# pemasok_air.net
KiCad netlist of a schematic drawn in EAGLE
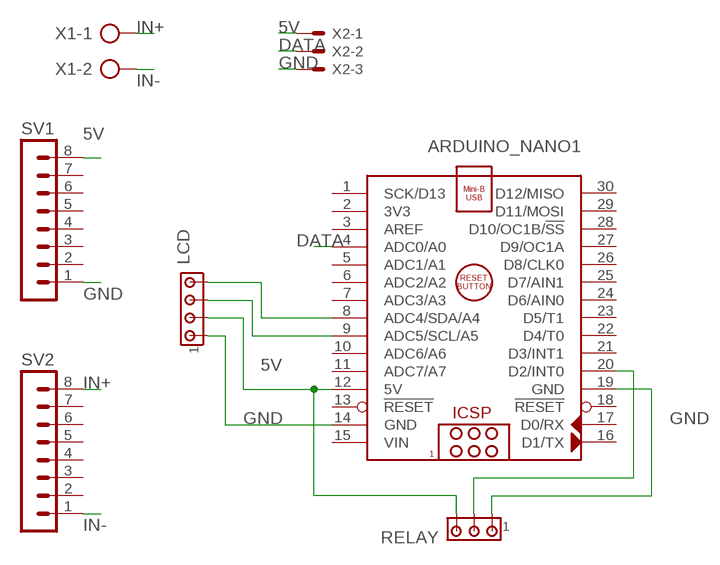
[diagram p0: schematic, sheet 1]

(export (version "E")
  (design (tool "Eeschema 10.0.6"))
  (components
    (comp (ref "ARDUINO_NANO1")
      (value "ARDUINO_NANO")
      (footprint "eagle-import:ARDUINO_NANO")
      (libsource (lib "eagle-import") (part "ARDUINO_NANO"))
    )
    (comp (ref "LCD")
      (value "MTA04-100")
      (footprint "eagle-import:10X04MTA")
      (libsource (lib "eagle-import") (part "MTA04-100"))
    )
    (comp (ref "RELAY")
      (value "MTA03-100")
      (footprint "eagle-import:10X03MTA")
      (libsource (lib "eagle-import") (part "MTA03-100"))
    )
    (comp (ref "SV1")
      (value "MA08-1")
      (footprint "eagle-import:MA08-1")
      (libsource (lib "eagle-import") (part "MA08-1"))
    )
    (comp (ref "SV2")
      (value "MA08-1")
      (footprint "eagle-import:MA08-1")
      (libsource (lib "eagle-import") (part "MA08-1"))
    )
    (comp (ref "X1")
      (value "AK500/2-H")
      (footprint "eagle-import:AK500_2-H")
      (libsource (lib "eagle-import") (part "AK500/2-H"))
    )
    (comp (ref "X2")
      (value "KK-156-3")
      (footprint "eagle-import:KK-156-3")
      (fields (field (name "MF") "MOLEX"))
      (libsource (lib "eagle-import") (part "KK-156-3"))
    )
  )
  (nets
    (net (code "1") (name "/5V") (class "Default")
      (node (ref "ARDUINO_NANO1") (pin "12") (pinfunction "5V_12") (pintype "power_in"))
      (node (ref "LCD") (pin "2") (pinfunction "2_2") (pintype "passive"))
      (node (ref "RELAY") (pin "3") (pinfunction "3_3") (pintype "passive"))
      (node (ref "SV1") (pin "8") (pinfunction "8_8") (pintype "passive"))
      (node (ref "X2") (pin "1") (pinfunction "S_1") (pintype "passive"))
    )
    (net (code "2") (name "/DATA") (class "Default")
      (node (ref "ARDUINO_NANO1") (pin "4") (pinfunction "ADC0/A0_4") (pintype "bidirectional"))
      (node (ref "X2") (pin "2") (pinfunction "S_2") (pintype "passive"))
    )
    (net (code "3") (name "/GND") (class "Default")
      (node (ref "ARDUINO_NANO1") (pin "14") (pinfunction "GND_14") (pintype "power_in"))
      (node (ref "ARDUINO_NANO1") (pin "19") (pinfunction "GND_19") (pintype "power_in"))
      (node (ref "LCD") (pin "1") (pinfunction "1_1") (pintype "passive"))
      (node (ref "RELAY") (pin "1") (pinfunction "1_1") (pintype "passive"))
      (node (ref "SV1") (pin "1") (pinfunction "1_1") (pintype "passive"))
      (node (ref "X2") (pin "3") (pinfunction "S_3") (pintype "passive"))
    )
    (net (code "4") (name "/IN+") (class "Default")
      (node (ref "SV2") (pin "8") (pinfunction "8_8") (pintype "passive"))
      (node (ref "X1") (pin "1") (pinfunction "KL_1") (pintype "passive"))
    )
    (net (code "5") (name "/IN-") (class "Default")
      (node (ref "SV2") (pin "1") (pinfunction "1_1") (pintype "passive"))
      (node (ref "X1") (pin "2") (pinfunction "KL_2") (pintype "passive"))
    )
    (net (code "6") (name "/VIN") (class "Default")
      (node (ref "ARDUINO_NANO1") (pin "15") (pinfunction "VIN_15") (pintype "power_in"))
    )
    (net (code "7") (name "Net-(ARDUINO_NANO1-ADC4{slash}SDA{slash}A4)") (class "Default")
      (node (ref "ARDUINO_NANO1") (pin "8") (pinfunction "ADC4/SDA/A4_8") (pintype "bidirectional"))
      (node (ref "LCD") (pin "4") (pinfunction "4_4") (pintype "passive"))
    )
    (net (code "8") (name "Net-(ARDUINO_NANO1-ADC5{slash}SCL{slash}A5)") (class "Default")
      (node (ref "ARDUINO_NANO1") (pin "9") (pinfunction "ADC5/SCL/A5_9") (pintype "bidirectional"))
      (node (ref "LCD") (pin "3") (pinfunction "3_3") (pintype "passive"))
    )
    (net (code "9") (name "Net-(ARDUINO_NANO1-D2{slash}INT0)") (class "Default")
      (node (ref "ARDUINO_NANO1") (pin "20") (pinfunction "D2/INT0_20") (pintype "bidirectional"))
      (node (ref "RELAY") (pin "2") (pinfunction "2_2") (pintype "passive"))
    )
    (net (code "10") (name "unconnected-(ARDUINO_NANO1-3V3-Pad2)") (class "Default")
      (node (ref "ARDUINO_NANO1") (pin "2") (pinfunction "3V3_2") (pintype "output"))
    )
    (net (code "11") (name "unconnected-(ARDUINO_NANO1-ADC1{slash}A1-Pad5)") (class "Default")
      (node (ref "ARDUINO_NANO1") (pin "5") (pinfunction "ADC1/A1_5") (pintype "bidirectional"))
    )
    (net (code "12") (name "unconnected-(ARDUINO_NANO1-ADC2{slash}A2-Pad6)") (class "Default")
      (node (ref "ARDUINO_NANO1") (pin "6") (pinfunction "ADC2/A2_6") (pintype "bidirectional"))
    )
    (net (code "13") (name "unconnected-(ARDUINO_NANO1-ADC3{slash}A3-Pad7)") (class "Default")
      (node (ref "ARDUINO_NANO1") (pin "7") (pinfunction "ADC3/A3_7") (pintype "bidirectional"))
    )
    (net (code "14") (name "unconnected-(ARDUINO_NANO1-ADC6{slash}A6-Pad10)") (class "Default")
      (node (ref "ARDUINO_NANO1") (pin "10") (pinfunction "ADC6/A6_10") (pintype "bidirectional"))
    )
    (net (code "15") (name "unconnected-(ARDUINO_NANO1-ADC7{slash}A7-Pad11)") (class "Default")
      (node (ref "ARDUINO_NANO1") (pin "11") (pinfunction "ADC7/A7_11") (pintype "bidirectional"))
    )
    (net (code "16") (name "unconnected-(ARDUINO_NANO1-AREF-Pad3)") (class "Default")
      (node (ref "ARDUINO_NANO1") (pin "3") (pinfunction "AREF_3") (pintype "input"))
    )
    (net (code "17") (name "unconnected-(ARDUINO_NANO1-D0{slash}RX-Pad17)") (class "Default")
      (node (ref "ARDUINO_NANO1") (pin "17") (pinfunction "D0/RX_17") (pintype "bidirectional"))
    )
    (net (code "18") (name "unconnected-(ARDUINO_NANO1-D1{slash}TX-Pad16)") (class "Default")
      (node (ref "ARDUINO_NANO1") (pin "16") (pinfunction "D1/TX_16") (pintype "bidirectional"))
    )
    (net (code "19") (name "unconnected-(ARDUINO_NANO1-D3{slash}INT1-Pad21)") (class "Default")
      (node (ref "ARDUINO_NANO1") (pin "21") (pinfunction "D3/INT1_21") (pintype "bidirectional"))
    )
    (net (code "20") (name "unconnected-(ARDUINO_NANO1-D4{slash}T0-Pad22)") (class "Default")
      (node (ref "ARDUINO_NANO1") (pin "22") (pinfunction "D4/T0_22") (pintype "bidirectional"))
    )
    (net (code "21") (name "unconnected-(ARDUINO_NANO1-D5{slash}T1-Pad23)") (class "Default")
      (node (ref "ARDUINO_NANO1") (pin "23") (pinfunction "D5/T1_23") (pintype "bidirectional"))
    )
    (net (code "22") (name "unconnected-(ARDUINO_NANO1-D6{slash}AIN0-Pad24)") (class "Default")
      (node (ref "ARDUINO_NANO1") (pin "24") (pinfunction "D6/AIN0_24") (pintype "bidirectional"))
    )
    (net (code "23") (name "unconnected-(ARDUINO_NANO1-D7{slash}AIN1-Pad25)") (class "Default")
      (node (ref "ARDUINO_NANO1") (pin "25") (pinfunction "D7/AIN1_25") (pintype "bidirectional"))
    )
    (net (code "24") (name "unconnected-(ARDUINO_NANO1-D8{slash}CLK0-Pad26)") (class "Default")
      (node (ref "ARDUINO_NANO1") (pin "26") (pinfunction "D8/CLK0_26") (pintype "bidirectional"))
    )
    (net (code "25") (name "unconnected-(ARDUINO_NANO1-D9{slash}OC1A-Pad27)") (class "Default")
      (node (ref "ARDUINO_NANO1") (pin "27") (pinfunction "D9/OC1A_27") (pintype "bidirectional"))
    )
    (net (code "26") (name "unconnected-(ARDUINO_NANO1-D10{slash}OC1B{slash}~{SS}-Pad28)") (class "Default")
      (node (ref "ARDUINO_NANO1") (pin "28") (pinfunction "D10/OC1B/~{SS}_28") (pintype "bidirectional"))
    )
    (net (code "27") (name "unconnected-(ARDUINO_NANO1-D11{slash}MOSI-Pad29)") (class "Default")
      (node (ref "ARDUINO_NANO1") (pin "29") (pinfunction "D11/MOSI_29") (pintype "bidirectional"))
    )
    (net (code "28") (name "unconnected-(ARDUINO_NANO1-D12{slash}MISO-Pad30)") (class "Default")
      (node (ref "ARDUINO_NANO1") (pin "30") (pinfunction "D12/MISO_30") (pintype "bidirectional"))
    )
    (net (code "29") (name "unconnected-(ARDUINO_NANO1-SCK{slash}D13-Pad1)") (class "Default")
      (node (ref "ARDUINO_NANO1") (pin "1") (pinfunction "SCK/D13_1") (pintype "bidirectional"))
    )
    (net (code "30") (name "unconnected-(ARDUINO_NANO1-~{RESET}-Pad13)") (class "Default")
      (node (ref "ARDUINO_NANO1") (pin "13") (pinfunction "~{RESET}_13") (pintype "input"))
    )
    (net (code "31") (name "unconnected-(ARDUINO_NANO1-~{RESET}-Pad18)") (class "Default")
      (node (ref "ARDUINO_NANO1") (pin "18") (pinfunction "~{RESET}_18") (pintype "input"))
    )
    (net (code "32") (name "unconnected-(SV1-Pad2)") (class "Default")
      (node (ref "SV1") (pin "2") (pinfunction "2_2") (pintype "passive"))
    )
    (net (code "33") (name "unconnected-(SV1-Pad3)") (class "Default")
      (node (ref "SV1") (pin "3") (pinfunction "3_3") (pintype "passive"))
    )
    (net (code "34") (name "unconnected-(SV1-Pad4)") (class "Default")
      (node (ref "SV1") (pin "4") (pinfunction "4_4") (pintype "passive"))
    )
    (net (code "35") (name "unconnected-(SV1-Pad5)") (class "Default")
      (node (ref "SV1") (pin "5") (pinfunction "5_5") (pintype "passive"))
    )
    (net (code "36") (name "unconnected-(SV1-Pad6)") (class "Default")
      (node (ref "SV1") (pin "6") (pinfunction "6_6") (pintype "passive"))
    )
    (net (code "37") (name "unconnected-(SV1-Pad7)") (class "Default")
      (node (ref "SV1") (pin "7") (pinfunction "7_7") (pintype "passive"))
    )
    (net (code "38") (name "unconnected-(SV2-Pad2)") (class "Default")
      (node (ref "SV2") (pin "2") (pinfunction "2_2") (pintype "passive"))
    )
    (net (code "39") (name "unconnected-(SV2-Pad3)") (class "Default")
      (node (ref "SV2") (pin "3") (pinfunction "3_3") (pintype "passive"))
    )
    (net (code "40") (name "unconnected-(SV2-Pad4)") (class "Default")
      (node (ref "SV2") (pin "4") (pinfunction "4_4") (pintype "passive"))
    )
    (net (code "41") (name "unconnected-(SV2-Pad5)") (class "Default")
      (node (ref "SV2") (pin "5") (pinfunction "5_5") (pintype "passive"))
    )
    (net (code "42") (name "unconnected-(SV2-Pad6)") (class "Default")
      (node (ref "SV2") (pin "6") (pinfunction "6_6") (pintype "passive"))
    )
    (net (code "43") (name "unconnected-(SV2-Pad7)") (class "Default")
      (node (ref "SV2") (pin "7") (pinfunction "7_7") (pintype "passive"))
    )
  )
)
